# mc_spine_con.net
KiCad netlist of a schematic drawn in Altium Designer
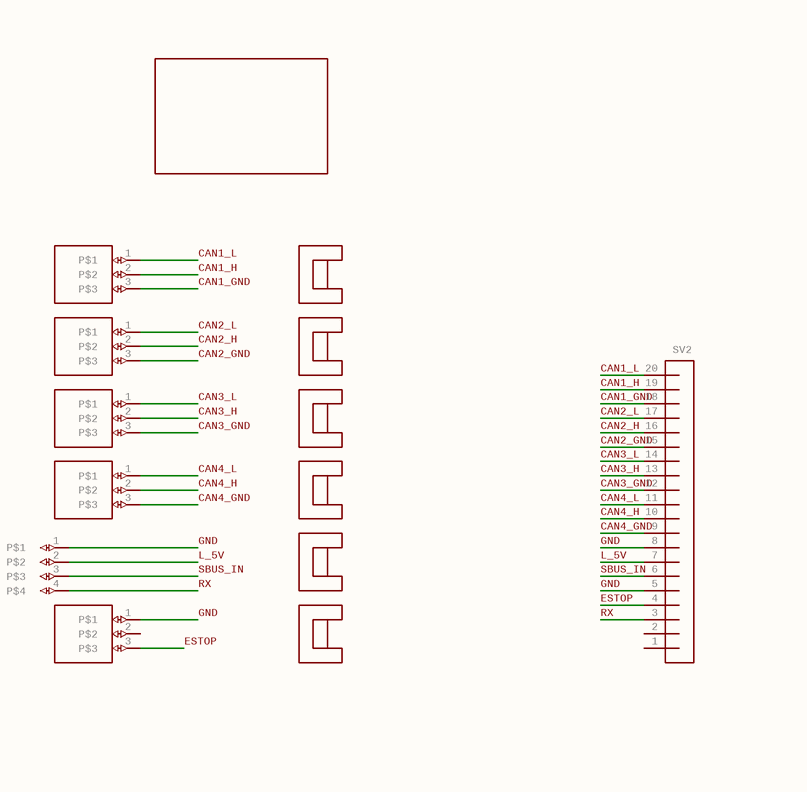
[diagram p0: mc_spine_con.SchDoc]

(export (version "E")
  (design (tool "Eeschema 10.0.6"))
  (components
    (comp (ref "SV2")
      (value "MA20-1L")
      (footprint "MA20-1L")
      (description "PIN HEADER")
      (fields (field (name "MF") "MF") (field (name "MPN") "MPN") (field (name "LIBRARYNAME") "con-lstb"))
      (libsource (lib "con-lstb") (part "MA20-1L"))
    )
    (comp (ref "U$1")
      (value "3-PIN")
      (footprint "M80-8430342")
      (fields (field (name "LIBRARYNAME") "Ben_Library"))
      (libsource (lib "Ben_Library") (part "3-PIN"))
    )
    (comp (ref "U$2")
      (value "UP_BOARD_NOPINS")
      (footprint "UP_BOARD_NOPINS")
      (fields (field (name "LIBRARYNAME") "Ben_Library"))
      (libsource (lib "Ben_Library") (part "UP_BOARD_NOPINS"))
    )
    (comp (ref "U$3")
      (value "3-PIN")
      (footprint "M80-8430342")
      (fields (field (name "LIBRARYNAME") "Ben_Library"))
      (libsource (lib "Ben_Library") (part "3-PIN"))
    )
    (comp (ref "U$4")
      (value "3-PIN")
      (footprint "M80-8430342")
      (fields (field (name "LIBRARYNAME") "Ben_Library"))
      (libsource (lib "Ben_Library") (part "3-PIN"))
    )
    (comp (ref "U$5")
      (value "4-PIN")
      (footprint "M80-8430442")
      (fields (field (name "LIBRARYNAME") "Ben_Library"))
      (libsource (lib "Ben_Library") (part "4-PIN"))
    )
    (comp (ref "U$6")
      (value "3-PIN")
      (footprint "M80-8430342")
      (fields (field (name "LIBRARYNAME") "Ben_Library"))
      (libsource (lib "Ben_Library") (part "3-PIN"))
    )
    (comp (ref "U$7")
      (value "SMD_CABLE_CLIPSS8111-46R")
      (footprint "S8111-46R")
      (fields (field (name "LIBRARYNAME") "Ben_Library"))
      (libsource (lib "Ben_Library") (part "SMD_CABLE_CLIPSS8111-46R"))
    )
    (comp (ref "U$8")
      (value "SMD_CABLE_CLIPSS8111-46R")
      (footprint "S8111-46R")
      (fields (field (name "LIBRARYNAME") "Ben_Library"))
      (libsource (lib "Ben_Library") (part "SMD_CABLE_CLIPSS8111-46R"))
    )
    (comp (ref "U$9")
      (value "SMD_CABLE_CLIPSS8111-46R")
      (footprint "S8111-46R")
      (fields (field (name "LIBRARYNAME") "Ben_Library"))
      (libsource (lib "Ben_Library") (part "SMD_CABLE_CLIPSS8111-46R"))
    )
    (comp (ref "U$10")
      (value "SMD_CABLE_CLIPSS8111-46R")
      (footprint "S8111-46R")
      (fields (field (name "LIBRARYNAME") "Ben_Library"))
      (libsource (lib "Ben_Library") (part "SMD_CABLE_CLIPSS8111-46R"))
    )
    (comp (ref "U$11")
      (value "SMD_CABLE_CLIPSS8111-46R")
      (footprint "S8111-46R")
      (fields (field (name "LIBRARYNAME") "Ben_Library"))
      (libsource (lib "Ben_Library") (part "SMD_CABLE_CLIPSS8111-46R"))
    )
    (comp (ref "U$12")
      (value "3-PIN")
      (footprint "M80-8430342")
      (fields (field (name "LIBRARYNAME") "Ben_Library"))
      (libsource (lib "Ben_Library") (part "3-PIN"))
    )
    (comp (ref "U$13")
      (value "SMD_CABLE_CLIPSS8111-46R")
      (footprint "S8111-46R")
      (fields (field (name "LIBRARYNAME") "Ben_Library"))
      (libsource (lib "Ben_Library") (part "SMD_CABLE_CLIPSS8111-46R"))
    )
  )
  (nets
    (net (code "1") (name "/CAN1_GND") (class "Default")
      (node (ref "SV2") (pin "18") (pinfunction "18_18") (pintype "passive"))
      (node (ref "U$12") (pin "3") (pinfunction "P$3_3") (pintype "bidirectional"))
    )
    (net (code "2") (name "/CAN1_H") (class "Default")
      (node (ref "SV2") (pin "19") (pinfunction "19_19") (pintype "passive"))
      (node (ref "U$12") (pin "2") (pinfunction "P$2_2") (pintype "bidirectional"))
    )
    (net (code "3") (name "/CAN1_L") (class "Default")
      (node (ref "SV2") (pin "20") (pinfunction "20_20") (pintype "passive"))
      (node (ref "U$12") (pin "1") (pinfunction "P$1_1") (pintype "bidirectional"))
    )
    (net (code "4") (name "/CAN2_GND") (class "Default")
      (node (ref "SV2") (pin "15") (pinfunction "15_15") (pintype "passive"))
      (node (ref "U$1") (pin "3") (pinfunction "P$3_3") (pintype "bidirectional"))
    )
    (net (code "5") (name "/CAN2_H") (class "Default")
      (node (ref "SV2") (pin "16") (pinfunction "16_16") (pintype "passive"))
      (node (ref "U$1") (pin "2") (pinfunction "P$2_2") (pintype "bidirectional"))
    )
    (net (code "6") (name "/CAN2_L") (class "Default")
      (node (ref "SV2") (pin "17") (pinfunction "17_17") (pintype "passive"))
      (node (ref "U$1") (pin "1") (pinfunction "P$1_1") (pintype "bidirectional"))
    )
    (net (code "7") (name "/CAN3_GND") (class "Default")
      (node (ref "SV2") (pin "12") (pinfunction "12_12") (pintype "passive"))
      (node (ref "U$3") (pin "3") (pinfunction "P$3_3") (pintype "bidirectional"))
    )
    (net (code "8") (name "/CAN3_H") (class "Default")
      (node (ref "SV2") (pin "13") (pinfunction "13_13") (pintype "passive"))
      (node (ref "U$3") (pin "2") (pinfunction "P$2_2") (pintype "bidirectional"))
    )
    (net (code "9") (name "/CAN3_L") (class "Default")
      (node (ref "SV2") (pin "14") (pinfunction "14_14") (pintype "passive"))
      (node (ref "U$3") (pin "1") (pinfunction "P$1_1") (pintype "bidirectional"))
    )
    (net (code "10") (name "/CAN4_GND") (class "Default")
      (node (ref "SV2") (pin "9") (pinfunction "9_9") (pintype "passive"))
      (node (ref "U$4") (pin "3") (pinfunction "P$3_3") (pintype "bidirectional"))
    )
    (net (code "11") (name "/CAN4_H") (class "Default")
      (node (ref "SV2") (pin "10") (pinfunction "10_10") (pintype "passive"))
      (node (ref "U$4") (pin "2") (pinfunction "P$2_2") (pintype "bidirectional"))
    )
    (net (code "12") (name "/CAN4_L") (class "Default")
      (node (ref "SV2") (pin "11") (pinfunction "11_11") (pintype "passive"))
      (node (ref "U$4") (pin "1") (pinfunction "P$1_1") (pintype "bidirectional"))
    )
    (net (code "13") (name "/ESTOP") (class "Default")
      (node (ref "SV2") (pin "4") (pinfunction "4_4") (pintype "passive"))
      (node (ref "U$6") (pin "3") (pinfunction "P$3_3") (pintype "bidirectional"))
    )
    (net (code "14") (name "/GND") (class "Default")
      (node (ref "SV2") (pin "5") (pinfunction "5_5") (pintype "passive"))
      (node (ref "SV2") (pin "8") (pinfunction "8_8") (pintype "passive"))
      (node (ref "U$5") (pin "1") (pinfunction "P$1_1") (pintype "bidirectional"))
      (node (ref "U$6") (pin "1") (pinfunction "P$1_1") (pintype "bidirectional"))
    )
    (net (code "15") (name "/L_5V") (class "Default")
      (node (ref "SV2") (pin "7") (pinfunction "7_7") (pintype "passive"))
      (node (ref "U$5") (pin "2") (pinfunction "P$2_2") (pintype "bidirectional"))
    )
    (net (code "16") (name "/RX") (class "Default")
      (node (ref "SV2") (pin "3") (pinfunction "3_3") (pintype "passive"))
      (node (ref "U$5") (pin "4") (pinfunction "P$4_4") (pintype "bidirectional"))
    )
    (net (code "17") (name "/SBUS_IN") (class "Default")
      (node (ref "SV2") (pin "6") (pinfunction "6_6") (pintype "passive"))
      (node (ref "U$5") (pin "3") (pinfunction "P$3_3") (pintype "bidirectional"))
    )
    (net (code "18") (name "unconnected-(SV2-Pad1)") (class "Default")
      (node (ref "SV2") (pin "1") (pinfunction "1_1") (pintype "passive"))
    )
    (net (code "19") (name "unconnected-(SV2-Pad2)") (class "Default")
      (node (ref "SV2") (pin "2") (pinfunction "2_2") (pintype "passive"))
    )
    (net (code "20") (name "unconnected-(U$6-P$2-Pad2)") (class "Default")
      (node (ref "U$6") (pin "2") (pinfunction "P$2_2") (pintype "bidirectional"))
    )
  )
)
